# droneSlave.net
KiCad netlist of a schematic drawn in EAGLE
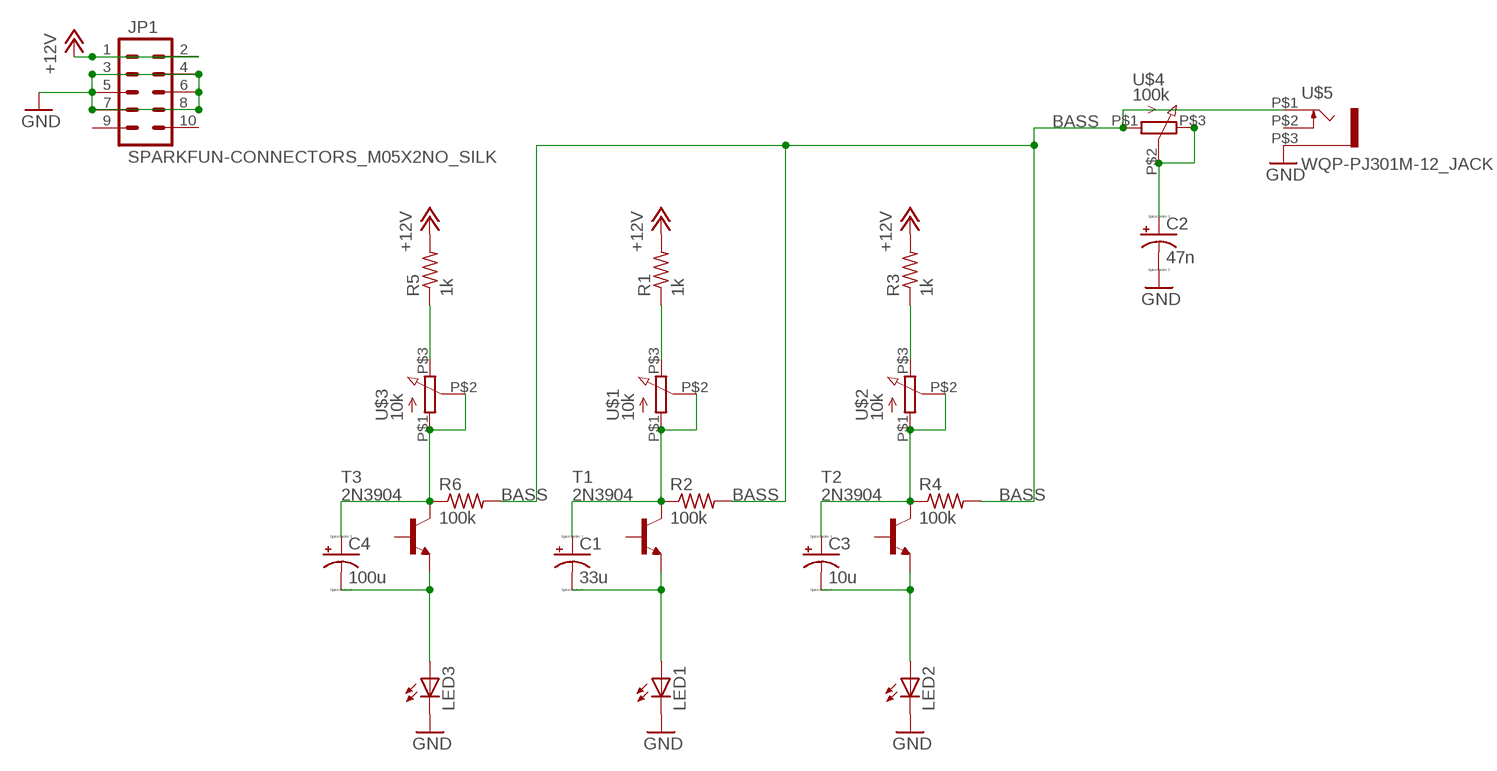
[diagram p0: schematic, sheet 1]

(export (version "E")
  (design (tool "Eeschema 10.0.6"))
  (components
    (comp (ref "C1")
      (value "33u")
      (footprint "eagle-import:E2,5-7")
      (libsource (lib "eagle-import") (part "CPOL-USE2.5-7"))
    )
    (comp (ref "C2")
      (value "47n")
      (footprint "eagle-import:E2,5-7")
      (libsource (lib "eagle-import") (part "CPOL-USE2.5-7"))
    )
    (comp (ref "C3")
      (value "10u")
      (footprint "eagle-import:E2,5-7")
      (libsource (lib "eagle-import") (part "CPOL-USE2.5-7"))
    )
    (comp (ref "C4")
      (value "100u")
      (footprint "eagle-import:E2,5-7")
      (libsource (lib "eagle-import") (part "CPOL-USE2.5-7"))
    )
    (comp (ref "JP1")
      (value "SPARKFUN-CONNECTORS_M05X2NO_SILK")
      (footprint "eagle-import:SPARKFUN-CONNECTORS_2X5_NOSILK")
      (libsource (lib "eagle-import") (part "SPARKFUN-CONNECTORS_M05X2NO_SILK"))
    )
    (comp (ref "LED1")
      (value "LED5MM")
      (footprint "eagle-import:LED5MM")
      (libsource (lib "eagle-import") (part "LED5MM"))
    )
    (comp (ref "LED2")
      (value "LED5MM")
      (footprint "eagle-import:LED5MM")
      (libsource (lib "eagle-import") (part "LED5MM"))
    )
    (comp (ref "LED3")
      (value "LED5MM")
      (footprint "eagle-import:LED5MM")
      (libsource (lib "eagle-import") (part "LED5MM"))
    )
    (comp (ref "R1")
      (value "1k")
      (footprint "eagle-import:0204_7")
      (libsource (lib "eagle-import") (part "R-US_0204/7"))
    )
    (comp (ref "R2")
      (value "100k")
      (footprint "eagle-import:0204_7")
      (libsource (lib "eagle-import") (part "R-US_0204/7"))
    )
    (comp (ref "R3")
      (value "1k")
      (footprint "eagle-import:0204_7")
      (libsource (lib "eagle-import") (part "R-US_0204/7"))
    )
    (comp (ref "R4")
      (value "100k")
      (footprint "eagle-import:0204_7")
      (libsource (lib "eagle-import") (part "R-US_0204/7"))
    )
    (comp (ref "R5")
      (value "1k")
      (footprint "eagle-import:0204_7")
      (libsource (lib "eagle-import") (part "R-US_0204/7"))
    )
    (comp (ref "R6")
      (value "100k")
      (footprint "eagle-import:0204_7")
      (libsource (lib "eagle-import") (part "R-US_0204/7"))
    )
    (comp (ref "T1")
      (value "2N3904")
      (footprint "eagle-import:TO92")
      (libsource (lib "eagle-import") (part "2N3904"))
    )
    (comp (ref "T2")
      (value "2N3904")
      (footprint "eagle-import:TO92")
      (libsource (lib "eagle-import") (part "2N3904"))
    )
    (comp (ref "T3")
      (value "2N3904")
      (footprint "eagle-import:TO92")
      (libsource (lib "eagle-import") (part "2N3904"))
    )
    (comp (ref "U$1")
      (value "10k")
      (footprint "eagle-import:INSTRUO_Q-POT")
      (libsource (lib "eagle-import") (part "INSTRUO_Q-POT"))
    )
    (comp (ref "U$2")
      (value "10k")
      (footprint "eagle-import:INSTRUO_Q-POT")
      (libsource (lib "eagle-import") (part "INSTRUO_Q-POT"))
    )
    (comp (ref "U$3")
      (value "10k")
      (footprint "eagle-import:INSTRUO_Q-POT")
      (libsource (lib "eagle-import") (part "INSTRUO_Q-POT"))
    )
    (comp (ref "U$4")
      (value "100k")
      (footprint "eagle-import:INSTRUO_Q-POT")
      (libsource (lib "eagle-import") (part "INSTRUO_Q-POT"))
    )
    (comp (ref "U$5")
      (value "WQP-PJ301M-12_JACK")
      (footprint "eagle-import:WQP-PJ301M-12_JACK")
      (libsource (lib "eagle-import") (part "WQP-PJ301M-12_JACK"))
    )
  )
  (nets
    (net (code "1") (name "+12V") (class "Default")
      (node (ref "JP1") (pin "1") (pinfunction "1_1") (pintype "passive"))
      (node (ref "JP1") (pin "2") (pinfunction "2_2") (pintype "passive"))
      (node (ref "R1") (pin "2") (pinfunction "2_2") (pintype "passive"))
      (node (ref "R3") (pin "2") (pinfunction "2_2") (pintype "passive"))
      (node (ref "R5") (pin "2") (pinfunction "2_2") (pintype "passive"))
    )
    (net (code "2") (name "/BASS") (class "Default")
      (node (ref "R2") (pin "2") (pinfunction "2_2") (pintype "passive"))
      (node (ref "R4") (pin "2") (pinfunction "2_2") (pintype "passive"))
      (node (ref "R6") (pin "2") (pinfunction "2_2") (pintype "passive"))
      (node (ref "U$4") (pin "P$1") (pinfunction "1_P$1") (pintype "passive"))
      (node (ref "U$5") (pin "P$1") (pinfunction "2_P$1") (pintype "passive"))
    )
    (net (code "3") (name "GND") (class "Default")
      (node (ref "C2") (pin "-") (pinfunction "-_-") (pintype "passive"))
      (node (ref "JP1") (pin "3") (pinfunction "3_3") (pintype "passive"))
      (node (ref "JP1") (pin "4") (pinfunction "4_4") (pintype "passive"))
      (node (ref "JP1") (pin "5") (pinfunction "5_5") (pintype "passive"))
      (node (ref "JP1") (pin "6") (pinfunction "6_6") (pintype "passive"))
      (node (ref "JP1") (pin "7") (pinfunction "7_7") (pintype "passive"))
      (node (ref "JP1") (pin "8") (pinfunction "8_8") (pintype "passive"))
      (node (ref "LED1") (pin "K") (pinfunction "C_K") (pintype "passive"))
      (node (ref "LED2") (pin "K") (pinfunction "C_K") (pintype "passive"))
      (node (ref "LED3") (pin "K") (pinfunction "C_K") (pintype "passive"))
      (node (ref "U$5") (pin "P$3") (pinfunction "1_P$3") (pintype "passive"))
    )
    (net (code "4") (name "Net-(T1-C)") (class "Default")
      (node (ref "C1") (pin "+") (pinfunction "+_+") (pintype "passive"))
      (node (ref "R2") (pin "1") (pinfunction "1_1") (pintype "passive"))
      (node (ref "T1") (pin "1") (pinfunction "C_1") (pintype "passive"))
      (node (ref "U$1") (pin "P$1") (pinfunction "1_P$1") (pintype "passive"))
      (node (ref "U$1") (pin "P$2") (pinfunction "2_P$2") (pintype "passive"))
    )
    (net (code "5") (name "Net-(T1-E)") (class "Default")
      (node (ref "C1") (pin "-") (pinfunction "-_-") (pintype "passive"))
      (node (ref "LED1") (pin "A") (pinfunction "A_A") (pintype "passive"))
      (node (ref "T1") (pin "3") (pinfunction "E_3") (pintype "passive"))
    )
    (net (code "6") (name "Net-(T2-C)") (class "Default")
      (node (ref "C3") (pin "+") (pinfunction "+_+") (pintype "passive"))
      (node (ref "R4") (pin "1") (pinfunction "1_1") (pintype "passive"))
      (node (ref "T2") (pin "1") (pinfunction "C_1") (pintype "passive"))
      (node (ref "U$2") (pin "P$1") (pinfunction "1_P$1") (pintype "passive"))
      (node (ref "U$2") (pin "P$2") (pinfunction "2_P$2") (pintype "passive"))
    )
    (net (code "7") (name "Net-(T2-E)") (class "Default")
      (node (ref "C3") (pin "-") (pinfunction "-_-") (pintype "passive"))
      (node (ref "LED2") (pin "A") (pinfunction "A_A") (pintype "passive"))
      (node (ref "T2") (pin "3") (pinfunction "E_3") (pintype "passive"))
    )
    (net (code "8") (name "Net-(T3-C)") (class "Default")
      (node (ref "C4") (pin "+") (pinfunction "+_+") (pintype "passive"))
      (node (ref "R6") (pin "1") (pinfunction "1_1") (pintype "passive"))
      (node (ref "T3") (pin "1") (pinfunction "C_1") (pintype "passive"))
      (node (ref "U$3") (pin "P$1") (pinfunction "1_P$1") (pintype "passive"))
      (node (ref "U$3") (pin "P$2") (pinfunction "2_P$2") (pintype "passive"))
    )
    (net (code "9") (name "Net-(T3-E)") (class "Default")
      (node (ref "C4") (pin "-") (pinfunction "-_-") (pintype "passive"))
      (node (ref "LED3") (pin "A") (pinfunction "A_A") (pintype "passive"))
      (node (ref "T3") (pin "3") (pinfunction "E_3") (pintype "passive"))
    )
    (net (code "10") (name "Net-(U$1-3)") (class "Default")
      (node (ref "R1") (pin "1") (pinfunction "1_1") (pintype "passive"))
      (node (ref "U$1") (pin "P$3") (pinfunction "3_P$3") (pintype "passive"))
    )
    (net (code "11") (name "Net-(U$2-3)") (class "Default")
      (node (ref "R3") (pin "1") (pinfunction "1_1") (pintype "passive"))
      (node (ref "U$2") (pin "P$3") (pinfunction "3_P$3") (pintype "passive"))
    )
    (net (code "12") (name "Net-(U$3-3)") (class "Default")
      (node (ref "R5") (pin "1") (pinfunction "1_1") (pintype "passive"))
      (node (ref "U$3") (pin "P$3") (pinfunction "3_P$3") (pintype "passive"))
    )
    (net (code "13") (name "Net-(U$4-2)") (class "Default")
      (node (ref "C2") (pin "+") (pinfunction "+_+") (pintype "passive"))
      (node (ref "U$4") (pin "P$2") (pinfunction "2_P$2") (pintype "passive"))
      (node (ref "U$4") (pin "P$3") (pinfunction "3_P$3") (pintype "passive"))
    )
    (net (code "14") (name "unconnected-(JP1-Pad9)") (class "Default")
      (node (ref "JP1") (pin "9") (pinfunction "9_9") (pintype "passive"))
    )
    (net (code "15") (name "unconnected-(JP1-Pad10)") (class "Default")
      (node (ref "JP1") (pin "10") (pinfunction "10_10") (pintype "passive"))
    )
    (net (code "16") (name "unconnected-(T1-B-Pad2)") (class "Default")
      (node (ref "T1") (pin "2") (pinfunction "B_2") (pintype "passive"))
    )
    (net (code "17") (name "unconnected-(T2-B-Pad2)") (class "Default")
      (node (ref "T2") (pin "2") (pinfunction "B_2") (pintype "passive"))
    )
    (net (code "18") (name "unconnected-(T3-B-Pad2)") (class "Default")
      (node (ref "T3") (pin "2") (pinfunction "B_2") (pintype "passive"))
    )
    (net (code "19") (name "unconnected-(U$5-3-PadP$2)") (class "Default")
      (node (ref "U$5") (pin "P$2") (pinfunction "3_P$2") (pintype "passive"))
    )
  )
)
